# bunny_light.net
KiCad netlist of a schematic drawn in EAGLE
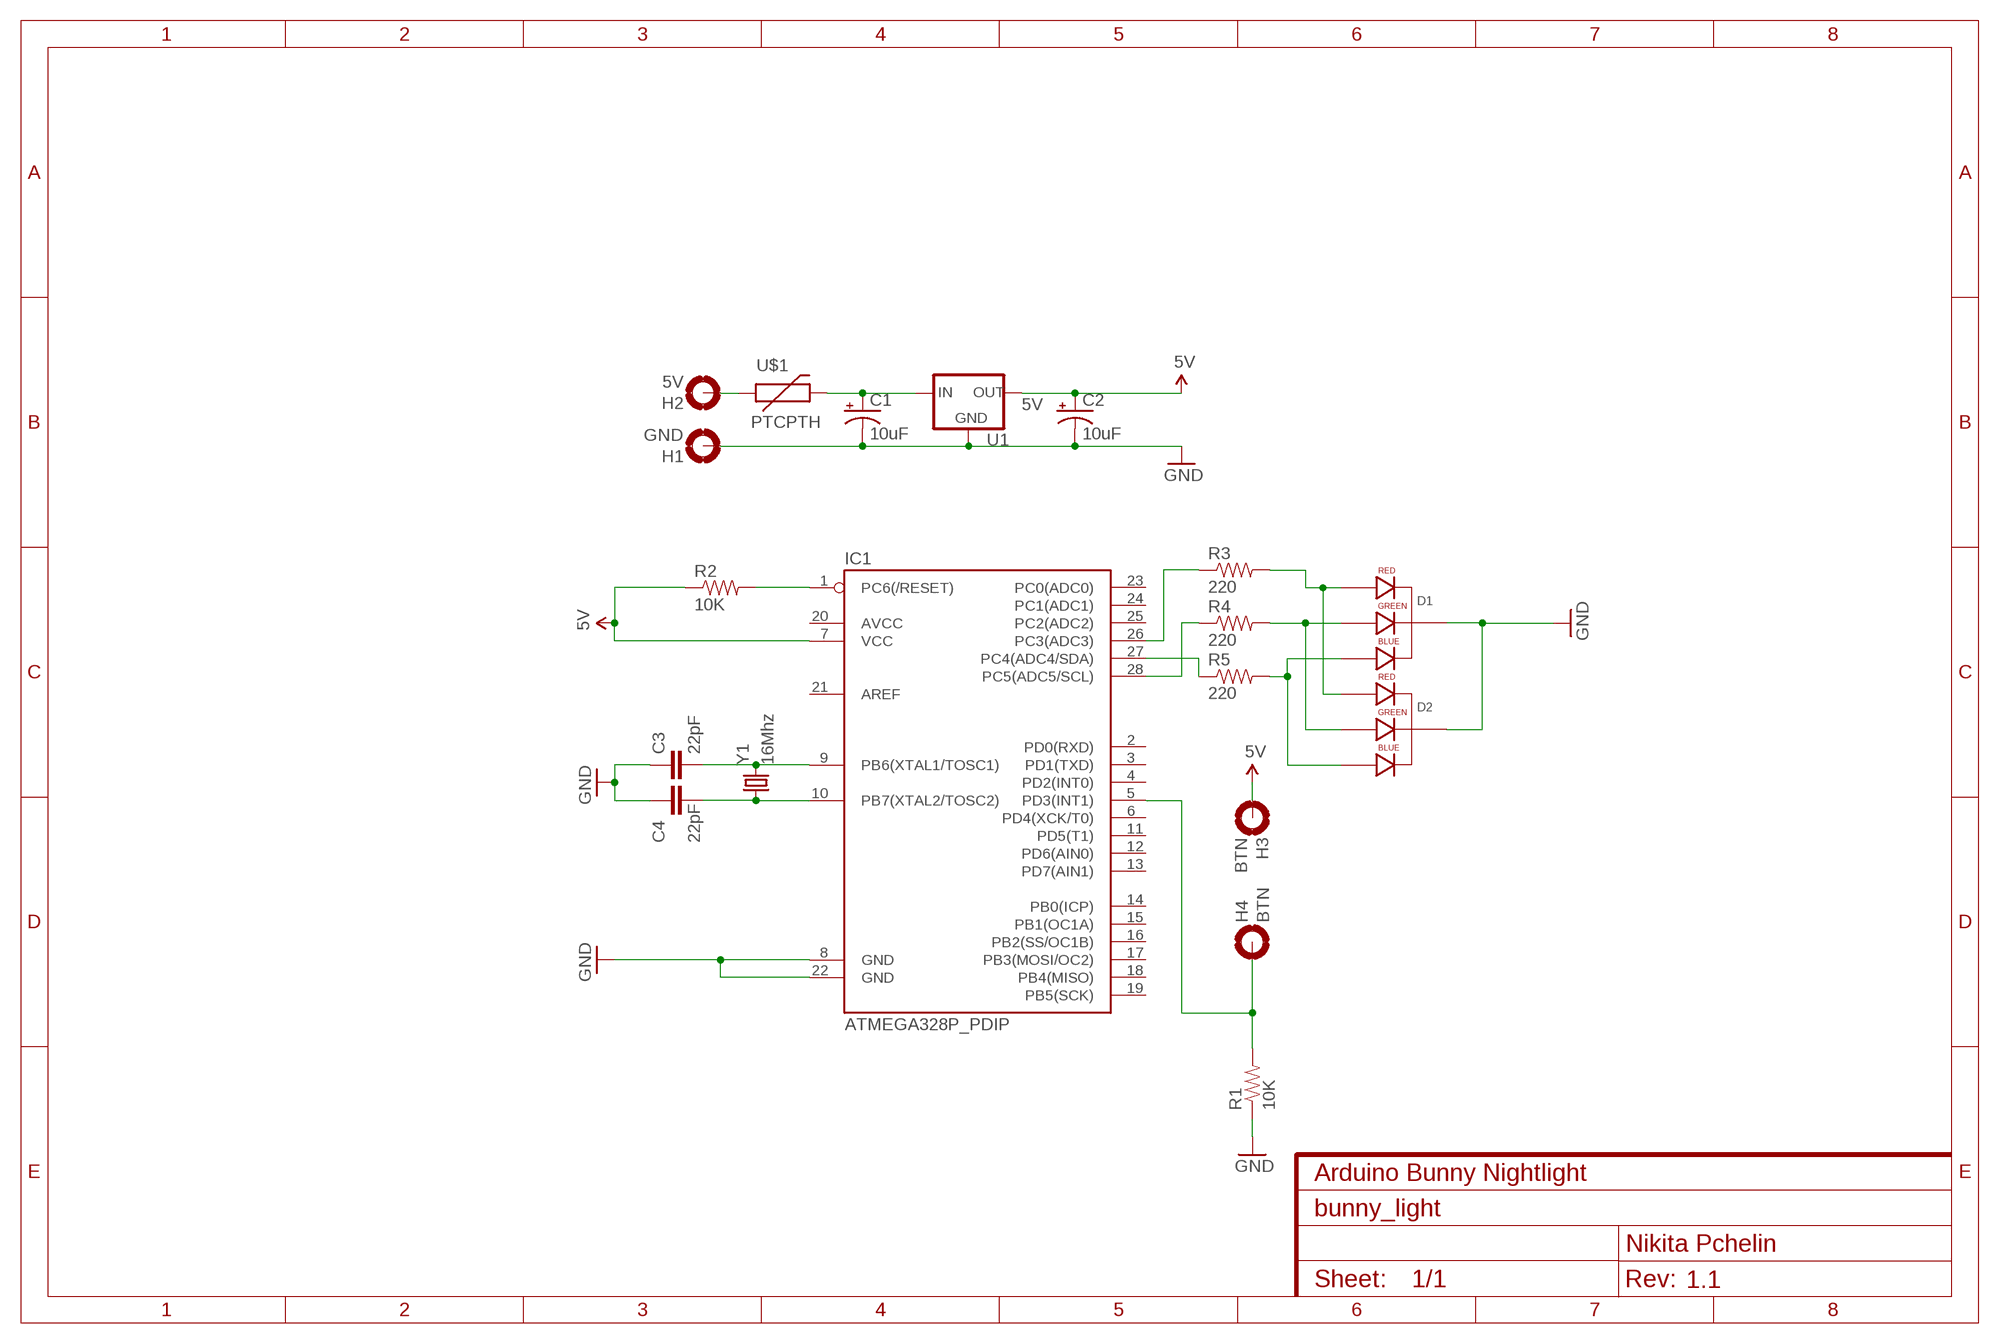
[diagram p0: schematic, sheet 1]

(export (version "E")
  (design (tool "Eeschema 10.0.6"))
  (components
    (comp (ref "C1")
      (value "10uF")
      (footprint "eagle-import:CPOL-RADIAL-100UF-25V")
      (libsource (lib "eagle-import") (part "CAP_POLPTH1"))
    )
    (comp (ref "C2")
      (value "10uF")
      (footprint "eagle-import:CPOL-RADIAL-100UF-25V")
      (libsource (lib "eagle-import") (part "CAP_POLPTH1"))
    )
    (comp (ref "C3")
      (value "22pF")
      (footprint "eagle-import:AXIAL-5MM")
      (libsource (lib "eagle-import") (part "CAP_"))
    )
    (comp (ref "C4")
      (value "22pF")
      (footprint "eagle-import:AXIAL-5MM")
      (libsource (lib "eagle-import") (part "CAP_"))
    )
    (comp (ref "D1")
      (value "LED-RGB-CC-THRUCLEAR")
      (footprint "eagle-import:LED-RGB-THRU")
      (libsource (lib "eagle-import") (part "LED-RGB-CC-THRUCLEAR"))
    )
    (comp (ref "D2")
      (value "LED-RGB-CC-THRUCLEAR")
      (footprint "eagle-import:LED-RGB-THRU")
      (libsource (lib "eagle-import") (part "LED-RGB-CC-THRUCLEAR"))
    )
    (comp (ref "H1")
      (value "GND")
      (footprint "eagle-import:2,8-PAD")
      (libsource (lib "eagle-import") (part "MOUNT-PAD-ROUND2.8"))
    )
    (comp (ref "H2")
      (value "5V")
      (footprint "eagle-import:2,8-PAD")
      (libsource (lib "eagle-import") (part "MOUNT-PAD-ROUND2.8"))
    )
    (comp (ref "H3")
      (value "BTN")
      (footprint "eagle-import:2,8-PAD")
      (libsource (lib "eagle-import") (part "MOUNT-PAD-ROUND2.8"))
    )
    (comp (ref "H4")
      (value "BTN")
      (footprint "eagle-import:2,8-PAD")
      (libsource (lib "eagle-import") (part "MOUNT-PAD-ROUND2.8"))
    )
    (comp (ref "IC1")
      (value "ATMEGA328P_PDIP")
      (footprint "eagle-import:DIL28-3")
      (libsource (lib "eagle-import") (part "ATMEGA328P_PDIP"))
    )
    (comp (ref "R1")
      (value "10K")
      (footprint "eagle-import:AXIAL-0.3EZ")
      (libsource (lib "eagle-import") (part "RESISTOREZ"))
    )
    (comp (ref "R2")
      (value "10K")
      (footprint "eagle-import:AXIAL-0.3EZ")
      (libsource (lib "eagle-import") (part "RESISTOREZ"))
    )
    (comp (ref "R3")
      (value "220")
      (footprint "eagle-import:AXIAL-0.3EZ")
      (libsource (lib "eagle-import") (part "RESISTOREZ"))
    )
    (comp (ref "R4")
      (value "220")
      (footprint "eagle-import:AXIAL-0.3EZ")
      (libsource (lib "eagle-import") (part "RESISTOREZ"))
    )
    (comp (ref "R5")
      (value "220")
      (footprint "eagle-import:AXIAL-0.3EZ")
      (libsource (lib "eagle-import") (part "RESISTOREZ"))
    )
    (comp (ref "U$1")
      (value "PTCPTH")
      (footprint "eagle-import:PTC")
      (libsource (lib "eagle-import") (part "PTCPTH"))
    )
    (comp (ref "U1")
      (value "5V")
      (footprint "eagle-import:78XXL")
      (libsource (lib "eagle-import") (part "V_REG_78XXSIDE"))
    )
    (comp (ref "Y1")
      (value "16Mhz")
      (footprint "eagle-import:HC49US")
      (libsource (lib "eagle-import") (part "CRYSTALHC49US"))
    )
  )
  (nets
    (net (code "1") (name "5V") (class "Default")
      (node (ref "C2") (pin "1") (pinfunction "+_1") (pintype "passive"))
      (node (ref "H3") (pin "B2,8") (pinfunction "MOUNT_B2,8") (pintype "passive"))
      (node (ref "IC1") (pin "7") (pinfunction "VCC_7") (pintype "bidirectional"))
      (node (ref "R2") (pin "P$1") (pinfunction "1_P$1") (pintype "passive"))
      (node (ref "U1") (pin "OUT") (pinfunction "OUT_OUT") (pintype "passive"))
    )
    (net (code "2") (name "GND") (class "Default")
      (node (ref "C1") (pin "2") (pinfunction "-_2") (pintype "passive"))
      (node (ref "C2") (pin "2") (pinfunction "-_2") (pintype "passive"))
      (node (ref "C3") (pin "P$1") (pinfunction "1_P$1") (pintype "passive"))
      (node (ref "C4") (pin "P$1") (pinfunction "1_P$1") (pintype "passive"))
      (node (ref "D1") (pin "2") (pinfunction "CATHODE_2") (pintype "bidirectional"))
      (node (ref "D2") (pin "2") (pinfunction "CATHODE_2") (pintype "bidirectional"))
      (node (ref "H1") (pin "B2,8") (pinfunction "MOUNT_B2,8") (pintype "passive"))
      (node (ref "IC1") (pin "22") (pinfunction "GND_22") (pintype "bidirectional"))
      (node (ref "IC1") (pin "8") (pinfunction "GND_8") (pintype "bidirectional"))
      (node (ref "R1") (pin "P$1") (pinfunction "1_P$1") (pintype "passive"))
      (node (ref "U1") (pin "GND") (pinfunction "GND_GND") (pintype "input"))
    )
    (net (code "3") (name "Net-(C1-+)") (class "Default")
      (node (ref "C1") (pin "1") (pinfunction "+_1") (pintype "passive"))
      (node (ref "U$1") (pin "P$2") (pinfunction "2_P$2") (pintype "bidirectional"))
      (node (ref "U1") (pin "IN") (pinfunction "IN_IN") (pintype "input"))
    )
    (net (code "4") (name "Net-(C3-2)") (class "Default")
      (node (ref "C3") (pin "P$2") (pinfunction "2_P$2") (pintype "passive"))
      (node (ref "IC1") (pin "9") (pinfunction "PB6(XTAL1/TOSC1)_9") (pintype "bidirectional"))
      (node (ref "Y1") (pin "2") (pinfunction "2_2") (pintype "passive"))
    )
    (net (code "5") (name "Net-(C4-2)") (class "Default")
      (node (ref "C4") (pin "P$2") (pinfunction "2_P$2") (pintype "passive"))
      (node (ref "IC1") (pin "10") (pinfunction "PB7(XTAL2/TOSC2)_10") (pintype "bidirectional"))
      (node (ref "Y1") (pin "1") (pinfunction "1_1") (pintype "passive"))
    )
    (net (code "6") (name "Net-(D1-BLUE_CATHODE)") (class "Default")
      (node (ref "D1") (pin "4") (pinfunction "BLUE_CATHODE_4") (pintype "bidirectional"))
      (node (ref "D2") (pin "4") (pinfunction "BLUE_CATHODE_4") (pintype "bidirectional"))
      (node (ref "R5") (pin "P$2") (pinfunction "2_P$2") (pintype "passive"))
    )
    (net (code "7") (name "Net-(D1-GREEN_CATHODE)") (class "Default")
      (node (ref "D1") (pin "3") (pinfunction "GREEN_CATHODE_3") (pintype "bidirectional"))
      (node (ref "D2") (pin "3") (pinfunction "GREEN_CATHODE_3") (pintype "bidirectional"))
      (node (ref "R4") (pin "P$2") (pinfunction "2_P$2") (pintype "passive"))
    )
    (net (code "8") (name "Net-(D1-RED_CATHODE)") (class "Default")
      (node (ref "D1") (pin "1") (pinfunction "RED_CATHODE_1") (pintype "bidirectional"))
      (node (ref "D2") (pin "1") (pinfunction "RED_CATHODE_1") (pintype "bidirectional"))
      (node (ref "R3") (pin "P$2") (pinfunction "2_P$2") (pintype "passive"))
    )
    (net (code "9") (name "Net-(H2-MOUNT)") (class "Default")
      (node (ref "H2") (pin "B2,8") (pinfunction "MOUNT_B2,8") (pintype "passive"))
      (node (ref "U$1") (pin "P$1") (pinfunction "1_P$1") (pintype "bidirectional"))
    )
    (net (code "10") (name "Net-(H4-MOUNT)") (class "Default")
      (node (ref "H4") (pin "B2,8") (pinfunction "MOUNT_B2,8") (pintype "passive"))
      (node (ref "IC1") (pin "5") (pinfunction "PD3(INT1)_5") (pintype "bidirectional"))
      (node (ref "R1") (pin "P$2") (pinfunction "2_P$2") (pintype "passive"))
    )
    (net (code "11") (name "Net-(IC1-PC3(ADC3))") (class "Default")
      (node (ref "IC1") (pin "26") (pinfunction "PC3(ADC3)_26") (pintype "bidirectional"))
      (node (ref "R3") (pin "P$1") (pinfunction "1_P$1") (pintype "passive"))
    )
    (net (code "12") (name "Net-(IC1-PC4(ADC4{slash}SDA))") (class "Default")
      (node (ref "IC1") (pin "27") (pinfunction "PC4(ADC4/SDA)_27") (pintype "bidirectional"))
      (node (ref "R5") (pin "P$1") (pinfunction "1_P$1") (pintype "passive"))
    )
    (net (code "13") (name "Net-(IC1-PC5(ADC5{slash}SCL))") (class "Default")
      (node (ref "IC1") (pin "28") (pinfunction "PC5(ADC5/SCL)_28") (pintype "bidirectional"))
      (node (ref "R4") (pin "P$1") (pinfunction "1_P$1") (pintype "passive"))
    )
    (net (code "14") (name "Net-(IC1-PC6({slash}RESET))") (class "Default")
      (node (ref "IC1") (pin "1") (pinfunction "PC6(/RESET)_1") (pintype "bidirectional"))
      (node (ref "R2") (pin "P$2") (pinfunction "2_P$2") (pintype "passive"))
    )
    (net (code "15") (name "unconnected-(IC1-AREF-Pad21)") (class "Default")
      (node (ref "IC1") (pin "21") (pinfunction "AREF_21") (pintype "bidirectional"))
    )
    (net (code "16") (name "unconnected-(IC1-AVCC-Pad20)") (class "Default")
      (node (ref "IC1") (pin "20") (pinfunction "AVCC_20") (pintype "bidirectional"))
    )
    (net (code "17") (name "unconnected-(IC1-PB0(ICP)-Pad14)") (class "Default")
      (node (ref "IC1") (pin "14") (pinfunction "PB0(ICP)_14") (pintype "bidirectional"))
    )
    (net (code "18") (name "unconnected-(IC1-PB1(OC1A)-Pad15)") (class "Default")
      (node (ref "IC1") (pin "15") (pinfunction "PB1(OC1A)_15") (pintype "bidirectional"))
    )
    (net (code "19") (name "unconnected-(IC1-PB2(SS{slash}OC1B)-Pad16)") (class "Default")
      (node (ref "IC1") (pin "16") (pinfunction "PB2(SS/OC1B)_16") (pintype "bidirectional"))
    )
    (net (code "20") (name "unconnected-(IC1-PB3(MOSI{slash}OC2)-Pad17)") (class "Default")
      (node (ref "IC1") (pin "17") (pinfunction "PB3(MOSI/OC2)_17") (pintype "bidirectional"))
    )
    (net (code "21") (name "unconnected-(IC1-PB4(MISO)-Pad18)") (class "Default")
      (node (ref "IC1") (pin "18") (pinfunction "PB4(MISO)_18") (pintype "bidirectional"))
    )
    (net (code "22") (name "unconnected-(IC1-PB5(SCK)-Pad19)") (class "Default")
      (node (ref "IC1") (pin "19") (pinfunction "PB5(SCK)_19") (pintype "bidirectional"))
    )
    (net (code "23") (name "unconnected-(IC1-PC0(ADC0)-Pad23)") (class "Default")
      (node (ref "IC1") (pin "23") (pinfunction "PC0(ADC0)_23") (pintype "bidirectional"))
    )
    (net (code "24") (name "unconnected-(IC1-PC1(ADC1)-Pad24)") (class "Default")
      (node (ref "IC1") (pin "24") (pinfunction "PC1(ADC1)_24") (pintype "bidirectional"))
    )
    (net (code "25") (name "unconnected-(IC1-PC2(ADC2)-Pad25)") (class "Default")
      (node (ref "IC1") (pin "25") (pinfunction "PC2(ADC2)_25") (pintype "bidirectional"))
    )
    (net (code "26") (name "unconnected-(IC1-PD0(RXD)-Pad2)") (class "Default")
      (node (ref "IC1") (pin "2") (pinfunction "PD0(RXD)_2") (pintype "bidirectional"))
    )
    (net (code "27") (name "unconnected-(IC1-PD1(TXD)-Pad3)") (class "Default")
      (node (ref "IC1") (pin "3") (pinfunction "PD1(TXD)_3") (pintype "bidirectional"))
    )
    (net (code "28") (name "unconnected-(IC1-PD2(INT0)-Pad4)") (class "Default")
      (node (ref "IC1") (pin "4") (pinfunction "PD2(INT0)_4") (pintype "bidirectional"))
    )
    (net (code "29") (name "unconnected-(IC1-PD4(XCK{slash}T0)-Pad6)") (class "Default")
      (node (ref "IC1") (pin "6") (pinfunction "PD4(XCK/T0)_6") (pintype "bidirectional"))
    )
    (net (code "30") (name "unconnected-(IC1-PD5(T1)-Pad11)") (class "Default")
      (node (ref "IC1") (pin "11") (pinfunction "PD5(T1)_11") (pintype "bidirectional"))
    )
    (net (code "31") (name "unconnected-(IC1-PD6(AIN0)-Pad12)") (class "Default")
      (node (ref "IC1") (pin "12") (pinfunction "PD6(AIN0)_12") (pintype "bidirectional"))
    )
    (net (code "32") (name "unconnected-(IC1-PD7(AIN1)-Pad13)") (class "Default")
      (node (ref "IC1") (pin "13") (pinfunction "PD7(AIN1)_13") (pintype "bidirectional"))
    )
  )
)
